# 40106-4069-Synth.net
KiCad netlist of a schematic drawn in EAGLE
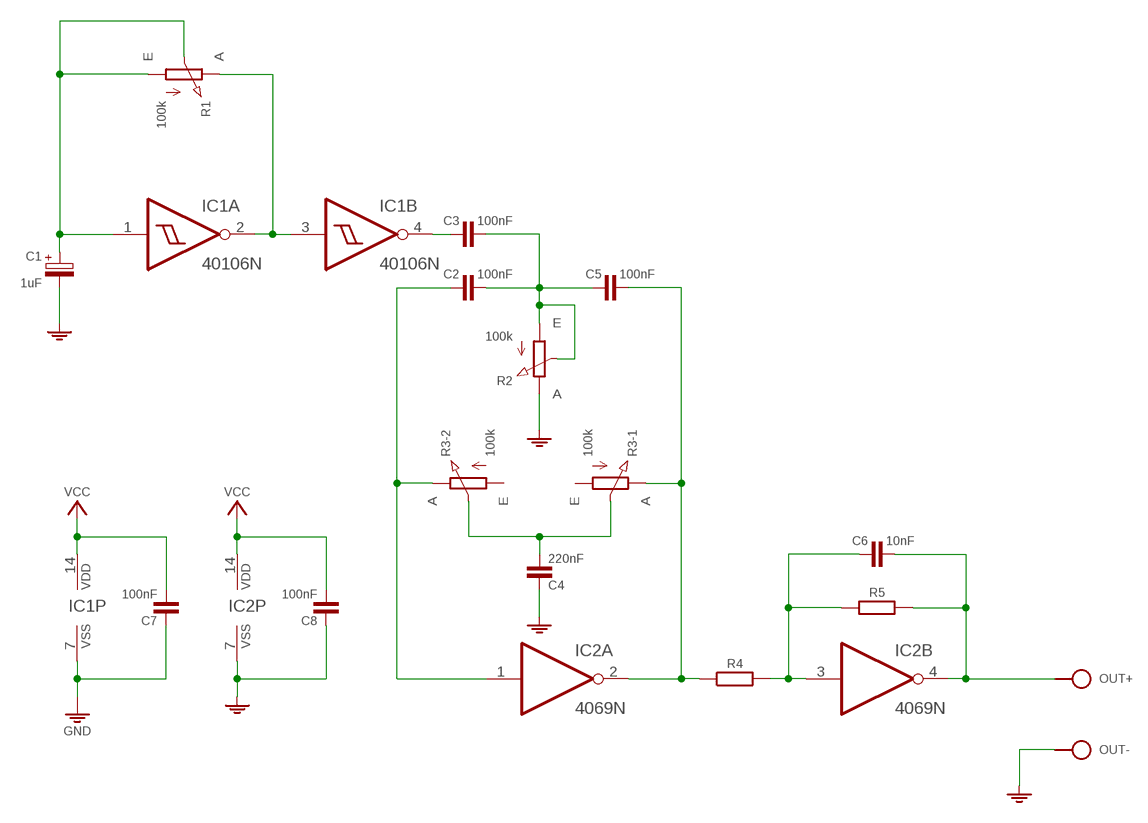
[diagram p0: schematic, sheet 1]

(export (version "E")
  (design (tool "Eeschema 10.0.6"))
  (components
    (comp (ref "C1")
      (value "1uF")
      (footprint "eagle-import:E2.5-4_V")
      (libsource (lib "eagle-import") (part "CPOLE2,5-4/V"))
    )
    (comp (ref "C2")
      (value "100nF")
      (footprint "eagle-import:C050-020X044")
      (libsource (lib "eagle-import") (part "C-H050-020X044"))
    )
    (comp (ref "C3")
      (value "100nF")
      (footprint "eagle-import:C050-020X044")
      (libsource (lib "eagle-import") (part "C-H050-020X044"))
    )
    (comp (ref "C4")
      (value "220nF")
      (footprint "eagle-import:C050-020X044_V")
      (libsource (lib "eagle-import") (part "C050-020X044/V"))
    )
    (comp (ref "C5")
      (value "100nF")
      (footprint "eagle-import:C050-020X044")
      (libsource (lib "eagle-import") (part "C-H050-020X044"))
    )
    (comp (ref "C6")
      (value "10nF")
      (footprint "eagle-import:C050-020X044")
      (libsource (lib "eagle-import") (part "C-H050-020X044"))
    )
    (comp (ref "C7")
      (value "100nF")
      (footprint "eagle-import:C050-020X044_V")
      (libsource (lib "eagle-import") (part "C050-020X044/V"))
    )
    (comp (ref "C8")
      (value "100nF")
      (footprint "eagle-import:C050-020X044_V")
      (libsource (lib "eagle-import") (part "C050-020X044/V"))
    )
    (comp (ref "IC1")
      (value "40106N")
      (footprint "eagle-import:DIL14")
      (libsource (lib "eagle-import") (part "40106N"))
    )
    (comp (ref "IC2")
      (value "4069N")
      (footprint "eagle-import:DIL14")
      (libsource (lib "eagle-import") (part "4069N"))
    )
    (comp (ref "J2")
      (value "VCC_GNDR")
      (footprint "eagle-import:SPAD+-")
      (libsource (lib "eagle-import") (part "VCC_GNDR"))
    )
    (comp (ref "OUT")
      (value "SPAD+--+")
      (footprint "eagle-import:SPAD-+")
      (libsource (lib "eagle-import") (part "SPAD+--+"))
    )
    (comp (ref "R1")
      (value "100k")
      (footprint "eagle-import:POT")
      (libsource (lib "eagle-import") (part "POT"))
    )
    (comp (ref "R2")
      (value "100k")
      (footprint "eagle-import:POT")
      (libsource (lib "eagle-import") (part "POT"))
    )
    (comp (ref "R3")
      (value "100k")
      (footprint "eagle-import:POT-STEREO-2X3")
      (libsource (lib "eagle-import") (part "POT-STEREO"))
    )
    (comp (ref "R4")
      (value "R-H0202/2V")
      (footprint "eagle-import:0202_2V")
      (libsource (lib "eagle-import") (part "R-H0202/2V"))
    )
    (comp (ref "R5")
      (value "R-H0204/10-V")
      (footprint "eagle-import:0204_10-V")
      (libsource (lib "eagle-import") (part "R-H0204/10-V"))
    )
  )
  (nets
    (net (code "1") (name "GND") (class "Default")
      (node (ref "C1") (pin "-") (pinfunction "-_-") (pintype "passive"))
      (node (ref "C4") (pin "1") (pinfunction "1_1") (pintype "passive"))
      (node (ref "C7") (pin "1") (pinfunction "1_1") (pintype "passive"))
      (node (ref "C8") (pin "1") (pinfunction "1_1") (pintype "passive"))
      (node (ref "IC1") (pin "7") (pinfunction "VSS_7") (pintype "power_in"))
      (node (ref "IC2") (pin "7") (pinfunction "VSS_7") (pintype "power_in"))
      (node (ref "J2") (pin "1") (pinfunction "GND_1") (pintype "power_in"))
      (node (ref "OUT") (pin "1") (pinfunction "P$1_1") (pintype "passive"))
      (node (ref "R2") (pin "E") (pinfunction "E_E") (pintype "passive"))
    )
    (net (code "2") (name "Net-(C2-Pad2)") (class "Default")
      (node (ref "C2") (pin "2") (pinfunction "2_2") (pintype "passive"))
      (node (ref "C3") (pin "2") (pinfunction "2_2") (pintype "passive"))
      (node (ref "C5") (pin "1") (pinfunction "1_1") (pintype "passive"))
      (node (ref "R2") (pin "A") (pinfunction "A_A") (pintype "passive"))
      (node (ref "R2") (pin "S") (pinfunction "S_S") (pintype "passive"))
    )
    (net (code "3") (name "Net-(IC1A-I)") (class "Default")
      (node (ref "C1") (pin "+") (pinfunction "+_+") (pintype "passive"))
      (node (ref "IC1") (pin "1") (pinfunction "I_1") (pintype "input"))
      (node (ref "R1") (pin "A") (pinfunction "A_A") (pintype "passive"))
      (node (ref "R1") (pin "S") (pinfunction "S_S") (pintype "passive"))
    )
    (net (code "4") (name "Net-(IC1A-O)") (class "Default")
      (node (ref "IC1") (pin "2") (pinfunction "O_2") (pintype "output"))
      (node (ref "IC1") (pin "3") (pinfunction "I_3") (pintype "input"))
      (node (ref "R1") (pin "E") (pinfunction "E_E") (pintype "passive"))
    )
    (net (code "5") (name "Net-(IC1B-O)") (class "Default")
      (node (ref "C3") (pin "1") (pinfunction "1_1") (pintype "passive"))
      (node (ref "IC1") (pin "4") (pinfunction "O_4") (pintype "output"))
    )
    (net (code "6") (name "Net-(IC2A-I)") (class "Default")
      (node (ref "C2") (pin "1") (pinfunction "1_1") (pintype "passive"))
      (node (ref "IC2") (pin "1") (pinfunction "I_1") (pintype "input"))
      (node (ref "R3") (pin "2-E") (pinfunction "E_2-E") (pintype "passive"))
    )
    (net (code "7") (name "Net-(IC2A-O)") (class "Default")
      (node (ref "C5") (pin "2") (pinfunction "2_2") (pintype "passive"))
      (node (ref "IC2") (pin "2") (pinfunction "O_2") (pintype "output"))
      (node (ref "R3") (pin "1-E") (pinfunction "E_1-E") (pintype "passive"))
      (node (ref "R4") (pin "1") (pinfunction "1_1") (pintype "passive"))
    )
    (net (code "8") (name "Net-(IC2B-I)") (class "Default")
      (node (ref "C6") (pin "1") (pinfunction "1_1") (pintype "passive"))
      (node (ref "IC2") (pin "3") (pinfunction "I_3") (pintype "input"))
      (node (ref "R4") (pin "2") (pinfunction "2_2") (pintype "passive"))
      (node (ref "R5") (pin "1") (pinfunction "1_1") (pintype "passive"))
    )
    (net (code "9") (name "Net-(IC2B-O)") (class "Default")
      (node (ref "C6") (pin "2") (pinfunction "2_2") (pintype "passive"))
      (node (ref "IC2") (pin "4") (pinfunction "O_4") (pintype "output"))
      (node (ref "OUT") (pin "2") (pinfunction "P$1_2") (pintype "passive"))
      (node (ref "R5") (pin "2") (pinfunction "2_2") (pintype "passive"))
    )
    (net (code "10") (name "Net-(R3A-S)") (class "Default")
      (node (ref "C4") (pin "2") (pinfunction "2_2") (pintype "passive"))
      (node (ref "R3") (pin "1-S") (pinfunction "S_1-S") (pintype "passive"))
      (node (ref "R3") (pin "2-S") (pinfunction "S_2-S") (pintype "passive"))
    )
    (net (code "11") (name "VCC") (class "Default")
      (node (ref "C7") (pin "2") (pinfunction "2_2") (pintype "passive"))
      (node (ref "C8") (pin "2") (pinfunction "2_2") (pintype "passive"))
      (node (ref "IC1") (pin "14") (pinfunction "VDD_14") (pintype "power_in"))
      (node (ref "IC2") (pin "14") (pinfunction "VDD_14") (pintype "power_in"))
      (node (ref "J2") (pin "2") (pinfunction "VCC_2") (pintype "power_in"))
    )
    (net (code "12") (name "unconnected-(R3A-A-Pad1-A)") (class "Default")
      (node (ref "R3") (pin "1-A") (pinfunction "A_1-A") (pintype "passive"))
    )
    (net (code "13") (name "unconnected-(R3B-A-Pad2-A)") (class "Default")
      (node (ref "R3") (pin "2-A") (pinfunction "A_2-A") (pintype "passive"))
    )
  )
)
